# POWER.net
KiCad netlist of a schematic drawn in Altium Designer
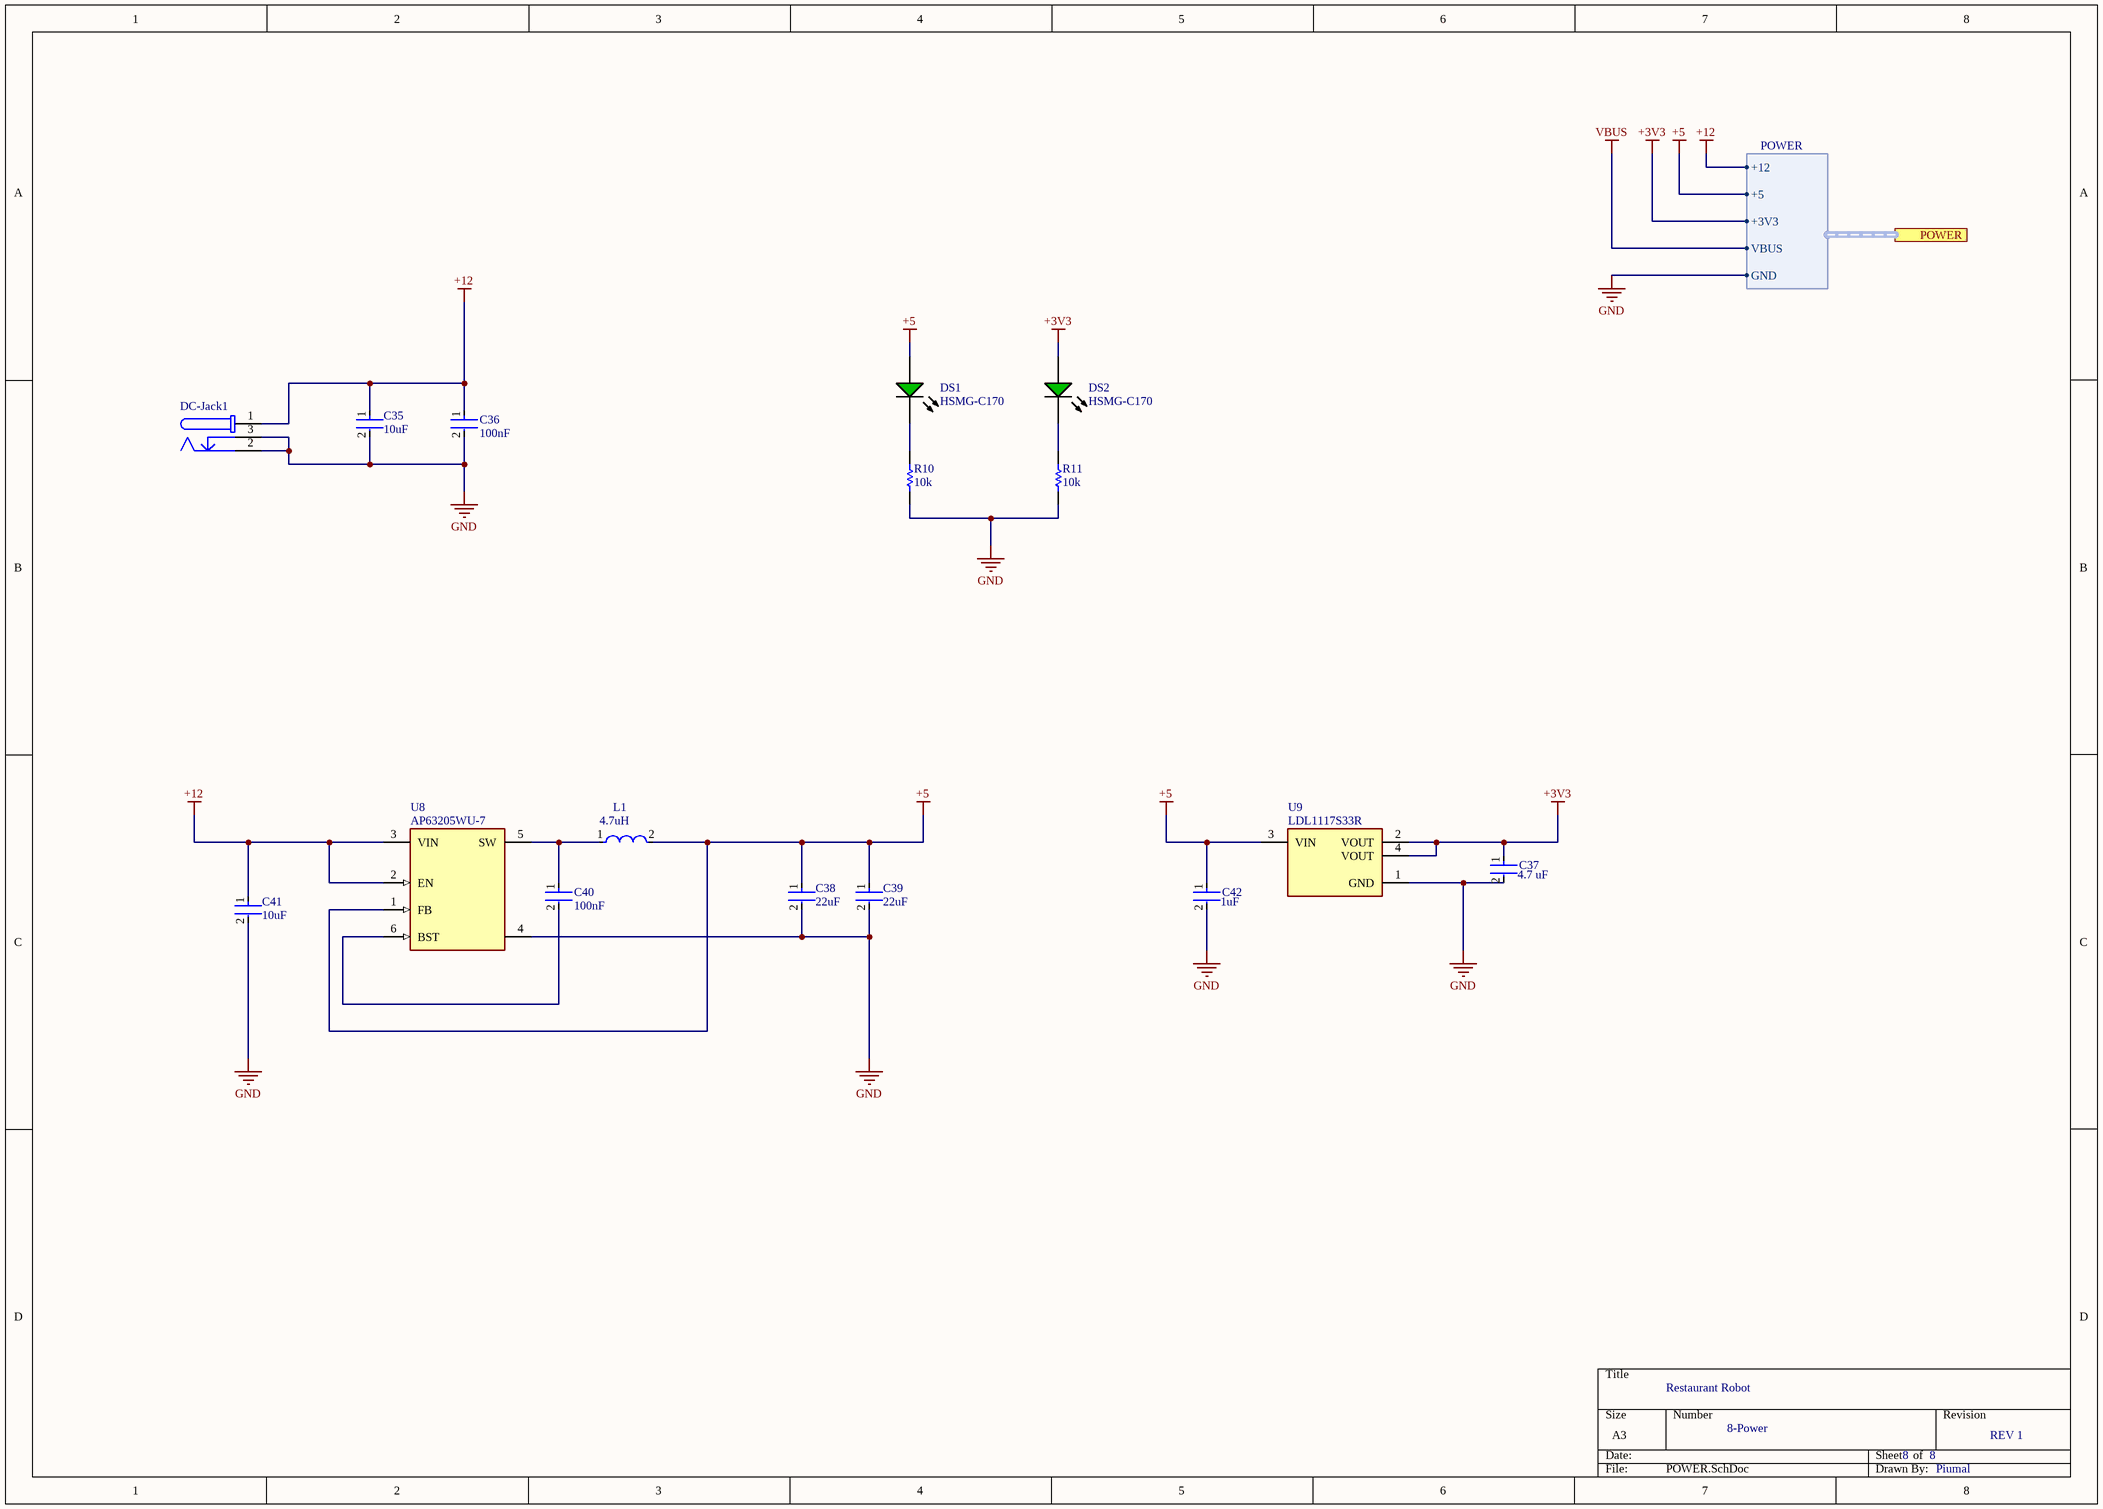
[diagram p0: POWER.SchDoc]

(export (version "E")
  (design (tool "Eeschema 10.0.6"))
  (components
    (comp (ref "C35")
      (value "1206ZD106KAT2A")
      (footprint "FP-1206-L_3_2_0_2-W_1_6_0-IPC_A")
      (description "General Purpose Ceramic Capacitor, 1206, 10uF, 10%, X5R, 15%, 10V")
      (fields
        (field (name "TOLERANCE") "10%")
        (field (name "VOLTAGE") "10V")
        (field (name "CAPACITANCE") "10uF")
      )
      (libsource (lib "Altium Content Vault") (part "02cd4be3c70576c341d710602a673aa"))
    )
    (comp (ref "C36")
      (value "100nF")
      (footprint "FP-0805-L_2_01_0_2-W_1_25-IPC_B")
      (description "Automotive Ceramic Capacitor, 0805, 100nF, 10%, X7R, 15%, 100V")
      (fields (field (name "TOLERANCE") "10%") (field (name "VOLTAGE") "100V"))
      (libsource (lib "Altium Content Vault") (part "b4654b650e69147ec39a6b967a45e02"))
    )
    (comp (ref "C37")
      (value "CC1206KKX7R9BB475")
      (footprint "FP-CC1206-1_25-MFG")
      (description "CAP CER 4.7UF 50V X7R 1206")
      (fields
        (field (name "TOLERANCE") "0.1")
        (field (name "CAPACITANCE") "4.7 uF")
        (field (name "MANUFACTURER") "Yageo")
      )
      (libsource (lib "Altium Content Vault") (part "11868f565c42a9108669ba33697ecf6"))
    )
    (comp (ref "C38")
      (value "C3216X5R1E226M160AB")
      (footprint "FP-C3216-160-0_2-IPC_B")
      (description "Multilayer Ceramic Capacitors 22uF ±20% 25V X5R SMD 1206")
      (fields (field (name "TOLERANCE") "20%") (field (name "CAPACITANCE") "22uF"))
      (libsource (lib "Altium Content Vault") (part "11868f565c42a9108669ba33697ecf6"))
    )
    (comp (ref "C39")
      (value "C3216X5R1E226M160AB")
      (footprint "FP-C3216-160-0_2-IPC_B")
      (description "Multilayer Ceramic Capacitors 22uF ±20% 25V X5R SMD 1206")
      (fields (field (name "TOLERANCE") "20%") (field (name "CAPACITANCE") "22uF"))
      (libsource (lib "Altium Content Vault") (part "11868f565c42a9108669ba33697ecf6"))
    )
    (comp (ref "C40")
      (value "100nF")
      (footprint "FP-0805-L_2_01_0_2-W_1_25-IPC_B")
      (description "Automotive Ceramic Capacitor, 0805, 100nF, 10%, X7R, 15%, 100V")
      (fields (field (name "TOLERANCE") "10%") (field (name "VOLTAGE") "100V"))
      (libsource (lib "Altium Content Vault") (part "b4654b650e69147ec39a6b967a45e02"))
    )
    (comp (ref "C41")
      (value "1206ZD106KAT2A")
      (footprint "FP-1206-L_3_2_0_2-W_1_6_0-IPC_A")
      (description "General Purpose Ceramic Capacitor, 1206, 10uF, 10%, X5R, 15%, 10V")
      (fields
        (field (name "TOLERANCE") "10%")
        (field (name "VOLTAGE") "10V")
        (field (name "CAPACITANCE") "10uF")
      )
      (libsource (lib "Altium Content Vault") (part "02cd4be3c70576c341d710602a673aa"))
    )
    (comp (ref "C42")
      (value "12065C105KAT2A")
      (footprint "FP-1206-L_3_2_0_2-W_1_6_0-IPC_A")
      (description "General Purpose Ceramic Capacitor, 1206, 1uF, 10%, X7R, 15%, 50V")
      (fields
        (field (name "CAPACITANCE") "1uF")
        (field (name "TOLERANCE") "10%")
        (field (name "VOLTAGE") "25V")
      )
      (libsource (lib "Altium Content Vault") (part "b4654b650e69147ec39a6b967a45e02"))
    )
    (comp (ref "DC-Jack1")
      (value "694106301002")
      (footprint "694106301002")
      (libsource (lib "Altium Content Vault") (part "DC Power Jack"))
    )
    (comp (ref "DS1")
      (value "HSMG-C170")
      (footprint "AVAG-HSMX-C170_V")
      (description "Chip LED, Green, 2.2 V, -40 to 85 degC, 2-Pin SMD, Pb-Free, Tape and Reel")
      (fields (field (name "MANUFACTURER") "Avago"))
      (libsource (lib "Altium Content Vault") (part "LED_GREEN_A1K2-2"))
    )
    (comp (ref "DS2")
      (value "HSMG-C170")
      (footprint "AVAG-HSMX-C170_V")
      (description "Chip LED, Green, 2.2 V, -40 to 85 degC, 2-Pin SMD, Pb-Free, Tape and Reel")
      (fields (field (name "MANUFACTURER") "Avago"))
      (libsource (lib "Altium Content Vault") (part "LED_GREEN_A1K2-2"))
    )
    (comp (ref "L1")
      (value "IHLP2525BDER4R7M01")
      (footprint "FP-IHLP-2525BD-FP_2_413x3-MFG")
      (description "Commercial Inductors, High Saturation Series 4.7uH 4.5A 63mΩ 20%")
      (fields (field (name "TOLERANCE") "20%") (field (name "INDUCTANCE") "4.7uH"))
      (libsource (lib "Altium Content Vault") (part "725321dda6339637d4d059423bc1c3c"))
    )
    (comp (ref "R10")
      (value "RC0805JR-0710KL")
      (footprint "RESC2013X60X35ML10T20")
      (description "Chip Resistor, 10 KOhm, +/- 5%, 0.125 W, -55 to 155 degC, 0805 (2012 Metric), RoHS, Tape and Reel")
      (fields (field (name "MANUFACTURER") "Yageo") (field (name "RESISTANCE") "10k"))
      (libsource (lib "Altium Content Vault") (part "RES-2"))
    )
    (comp (ref "R11")
      (value "RC0805JR-0710KL")
      (footprint "RESC2013X60X35ML10T20")
      (description "Chip Resistor, 10 KOhm, +/- 5%, 0.125 W, -55 to 155 degC, 0805 (2012 Metric), RoHS, Tape and Reel")
      (fields (field (name "MANUFACTURER") "Yageo") (field (name "RESISTANCE") "10k"))
      (libsource (lib "Altium Content Vault") (part "RES-2"))
    )
    (comp (ref "U8")
      (value "AP63205WU-7")
      (footprint "FP-TSOT26-MFG")
      (description "IC REG BUCK 5V 2A TSOT26")
      (fields
        (field (name "MANUFACTURER") "Diodes Inc.")
        (field (name "OCTOPART") "https://octopart.com/ap63205wu-7-diodes+inc.-98099551")
      )
      (libsource (lib "Altium Content Vault") (part "029bc9fbfa4a99dbb8b3a24c2adb655"))
    )
    (comp (ref "U9")
      (value "LDL1117S33R")
      (footprint "FP-SOT223-0046067-IPC_C")
      (description "IC REG LINEAR 3.3V 1.2A SOT223")
      (fields
        (field (name "OCTOPART") "https://octopart.com/ldl1117s33r-stmicroelectronics-81876163")
        (field (name "MANUFACTURER") "STMicroelectronics")
      )
      (libsource (lib "Altium Content Vault") (part "a602d55cb6d43002de8a72f1c695f0a"))
    )
  )
  (nets
    (net (code "2") (name "+3V3") (class "Default")
      (node (ref "C37") (pin "1") (pinfunction "1_1") (pintype "passive"))
      (node (ref "DS2") (pin "1") (pinfunction "A_1") (pintype "passive"))
      (node (ref "U9") (pin "2") (pinfunction "VOUT_2") (pintype "passive"))
      (node (ref "U9") (pin "4") (pinfunction "VOUT_4") (pintype "passive"))
    )
    (net (code "3") (name "+5") (class "Default")
      (node (ref "C38") (pin "1") (pinfunction "1_1") (pintype "passive"))
      (node (ref "C39") (pin "1") (pinfunction "1_1") (pintype "passive"))
      (node (ref "C42") (pin "1") (pinfunction "1_1") (pintype "passive"))
      (node (ref "DS1") (pin "1") (pinfunction "A_1") (pintype "passive"))
      (node (ref "L1") (pin "2") (pinfunction "2_2") (pintype "passive"))
      (node (ref "U8") (pin "1") (pinfunction "FB_1") (pintype "input"))
      (node (ref "U9") (pin "3") (pinfunction "VIN_3") (pintype "power_in"))
    )
    (net (code "4") (name "+12") (class "Default")
      (node (ref "C35") (pin "1") (pinfunction "1_1") (pintype "passive"))
      (node (ref "C36") (pin "1") (pinfunction "1_1") (pintype "passive"))
      (node (ref "C41") (pin "1") (pinfunction "1_1") (pintype "passive"))
      (node (ref "DC-Jack1") (pin "1") (pinfunction "1_1") (pintype "passive"))
      (node (ref "U8") (pin "2") (pinfunction "EN_2") (pintype "input"))
      (node (ref "U8") (pin "3") (pinfunction "VIN_3") (pintype "power_in"))
    )
    (net (code "6") (name "GND") (class "Default")
      (node (ref "C35") (pin "2") (pinfunction "2_2") (pintype "passive"))
      (node (ref "C36") (pin "2") (pinfunction "2_2") (pintype "passive"))
      (node (ref "C37") (pin "2") (pinfunction "2_2") (pintype "passive"))
      (node (ref "C38") (pin "2") (pinfunction "2_2") (pintype "passive"))
      (node (ref "C39") (pin "2") (pinfunction "2_2") (pintype "passive"))
      (node (ref "C41") (pin "2") (pinfunction "2_2") (pintype "passive"))
      (node (ref "C42") (pin "2") (pinfunction "2_2") (pintype "passive"))
      (node (ref "DC-Jack1") (pin "2") (pinfunction "2_2") (pintype "passive"))
      (node (ref "DC-Jack1") (pin "3") (pinfunction "3_3") (pintype "passive"))
      (node (ref "R10") (pin "2") (pinfunction "2_2") (pintype "passive"))
      (node (ref "R11") (pin "2") (pinfunction "2_2") (pintype "passive"))
      (node (ref "U8") (pin "4") (pinfunction "GND_4") (pintype "power_in"))
      (node (ref "U9") (pin "1") (pinfunction "GND_1") (pintype "power_in"))
    )
    (net (code "7") (name "Net-(DS1-K)") (class "Default")
      (node (ref "DS1") (pin "2") (pinfunction "K_2") (pintype "passive"))
      (node (ref "R10") (pin "1") (pinfunction "1_1") (pintype "passive"))
    )
    (net (code "8") (name "Net-(DS2-K)") (class "Default")
      (node (ref "DS2") (pin "2") (pinfunction "K_2") (pintype "passive"))
      (node (ref "R11") (pin "1") (pinfunction "1_1") (pintype "passive"))
    )
    (net (code "9") (name "Net-(U8-BST)") (class "Default")
      (node (ref "C40") (pin "2") (pinfunction "2_2") (pintype "passive"))
      (node (ref "U8") (pin "6") (pinfunction "BST_6") (pintype "input"))
    )
    (net (code "10") (name "Net-(U8-SW)") (class "Default")
      (node (ref "C40") (pin "1") (pinfunction "1_1") (pintype "passive"))
      (node (ref "L1") (pin "1") (pinfunction "1_1") (pintype "passive"))
      (node (ref "U8") (pin "5") (pinfunction "SW_5") (pintype "power_in"))
    )
  )
)
